# W5500.net
KiCad netlist of a schematic drawn in Altium Designer
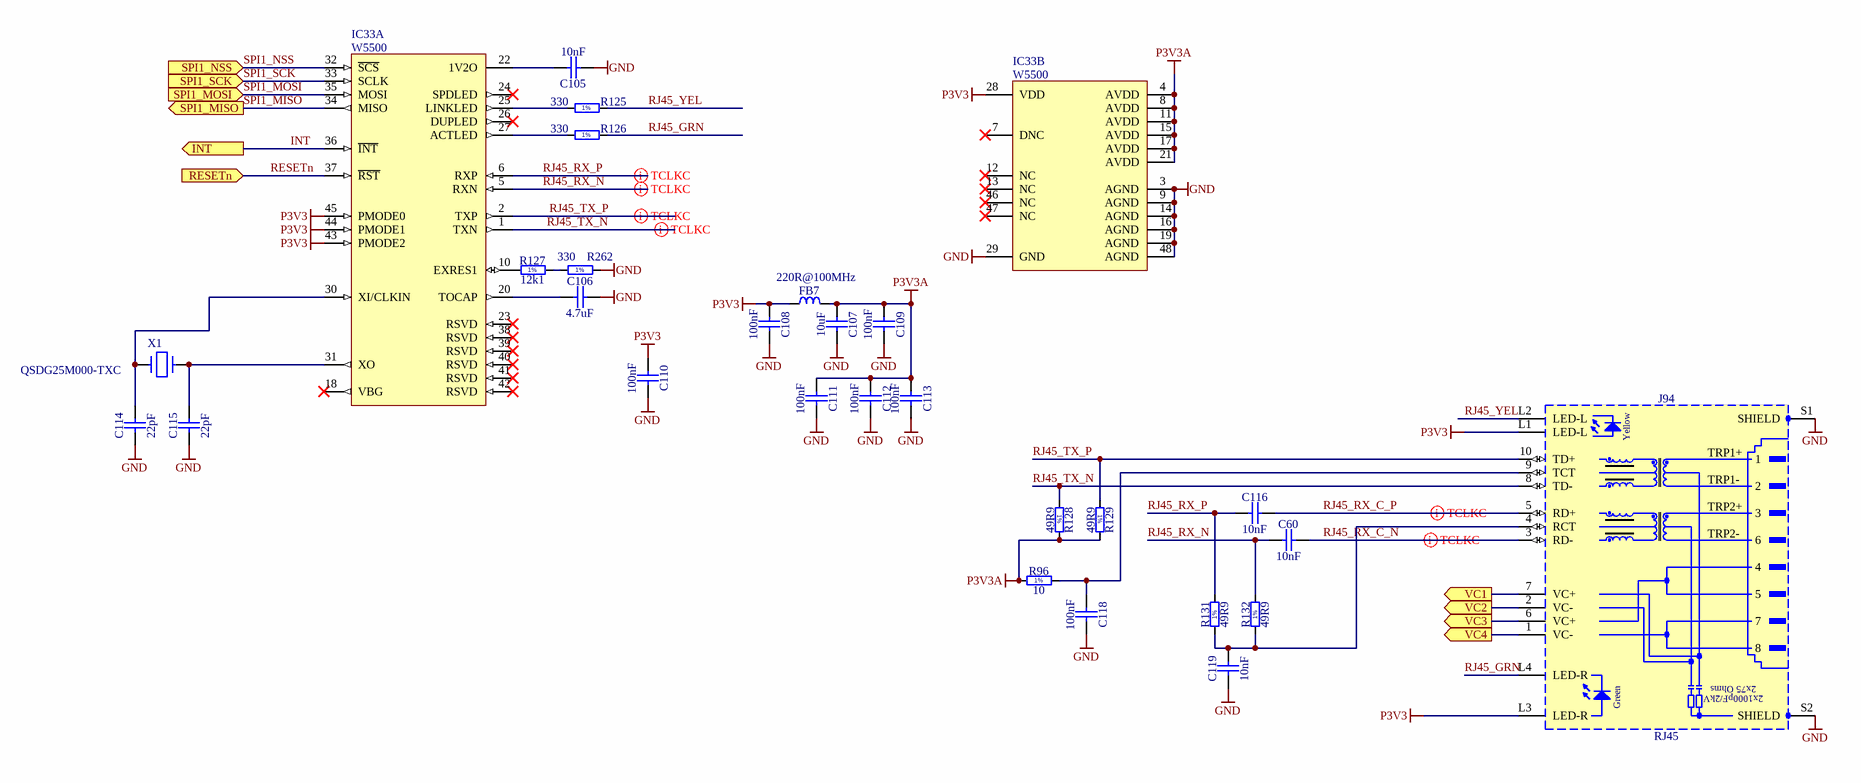
[diagram p0: W5500.SchDoc]

(export (version "E")
  (design (tool "Eeschema 10.0.6"))
  (components
    (comp (ref "C60")
      (value "10nF")
      (footprint "CAPC1608X87N")
      (description "Non-polarised capacitor")
      (fields
        (field (name "PART NUMBER") "CC0603_10NF_50V_5%_C0G")
        (field (name "VOLTAGE") "50V")
        (field (name "AUTHOR") "CERN DEM JLC")
      )
      (libsource (lib "Capacitors") (part "Capacitor - non polarized"))
    )
    (comp (ref "C105")
      (value "10nF")
      (footprint "CAPC1608X87N")
      (description "Non-polarised capacitor")
      (fields
        (field (name "PART NUMBER") "CC0603_10NF_50V_5%_C0G")
        (field (name "VOLTAGE") "50V")
        (field (name "AUTHOR") "CERN DEM JLC")
      )
      (libsource (lib "Capacitors") (part "Capacitor - non polarized"))
    )
    (comp (ref "C106")
      (value "4.7uF")
      (footprint "CAPC1608X90N")
      (description "Non-polarised capacitor")
      (fields
        (field (name "PART NUMBER") "CC0603_4.7UF_25V_10%_X5R")
        (field (name "VOLTAGE") "25V")
        (field (name "AUTHOR") "CERN DEM JLC")
      )
      (libsource (lib "Capacitors") (part "Capacitor - non polarized"))
    )
    (comp (ref "C107")
      (value "10uF")
      (footprint "CAPC2012X135N")
      (description "Non-polarised capacitor")
      (fields
        (field (name "PART NUMBER") "CC0805_10UF_16V_10%_X5R")
        (field (name "VOLTAGE") "16V")
        (field (name "AUTHOR") "CERN DEM JLC")
      )
      (libsource (lib "Capacitors") (part "Capacitor - non polarized"))
    )
    (comp (ref "C108")
      (value "100nF")
      (footprint "CAPC1005X55N")
      (description "Non-polarised capacitor")
      (fields
        (field (name "PART NUMBER") "CC0402_100NF_16V_10%_X7R")
        (field (name "VOLTAGE") "16V")
        (field (name "AUTHOR") "CERN DEM JLC")
      )
      (libsource (lib "Capacitors") (part "Capacitor - non polarized"))
    )
    (comp (ref "C109")
      (value "100nF")
      (footprint "CAPC1005X55N")
      (description "Non-polarised capacitor")
      (fields
        (field (name "PART NUMBER") "CC0402_100NF_16V_10%_X7R")
        (field (name "VOLTAGE") "16V")
        (field (name "AUTHOR") "CERN DEM JLC")
      )
      (libsource (lib "Capacitors") (part "Capacitor - non polarized"))
    )
    (comp (ref "C110")
      (value "100nF")
      (footprint "CAPC1005X55N")
      (description "Non-polarised capacitor")
      (fields
        (field (name "PART NUMBER") "CC0402_100NF_16V_10%_X7R")
        (field (name "VOLTAGE") "16V")
        (field (name "AUTHOR") "CERN DEM JLC")
      )
      (libsource (lib "Capacitors") (part "Capacitor - non polarized"))
    )
    (comp (ref "C111")
      (value "100nF")
      (footprint "CAPC1005X55N")
      (description "Non-polarised capacitor")
      (fields
        (field (name "PART NUMBER") "CC0402_100NF_16V_10%_X7R")
        (field (name "VOLTAGE") "16V")
        (field (name "AUTHOR") "CERN DEM JLC")
      )
      (libsource (lib "Capacitors") (part "Capacitor - non polarized"))
    )
    (comp (ref "C112")
      (value "100nF")
      (footprint "CAPC1005X55N")
      (description "Non-polarised capacitor")
      (fields
        (field (name "PART NUMBER") "CC0402_100NF_16V_10%_X7R")
        (field (name "VOLTAGE") "16V")
        (field (name "AUTHOR") "CERN DEM JLC")
      )
      (libsource (lib "Capacitors") (part "Capacitor - non polarized"))
    )
    (comp (ref "C113")
      (value "100nF")
      (footprint "CAPC1005X55N")
      (description "Non-polarised capacitor")
      (fields
        (field (name "PART NUMBER") "CC0402_100NF_16V_10%_X7R")
        (field (name "VOLTAGE") "16V")
        (field (name "AUTHOR") "CERN DEM JLC")
      )
      (libsource (lib "Capacitors") (part "Capacitor - non polarized"))
    )
    (comp (ref "C114")
      (value "22pF")
      (footprint "CAPC1005X55N")
      (description "Non-polarised capacitor")
      (fields
        (field (name "PART NUMBER") "CC0402_22PF_50V_5%_NP0")
        (field (name "VOLTAGE") "50V")
        (field (name "AUTHOR") "CERN DEM JLC")
      )
      (libsource (lib "Capacitors") (part "Capacitor - non polarized"))
    )
    (comp (ref "C115")
      (value "22pF")
      (footprint "CAPC1005X55N")
      (description "Non-polarised capacitor")
      (fields
        (field (name "PART NUMBER") "CC0402_22PF_50V_5%_NP0")
        (field (name "VOLTAGE") "50V")
        (field (name "AUTHOR") "CERN DEM JLC")
      )
      (libsource (lib "Capacitors") (part "Capacitor - non polarized"))
    )
    (comp (ref "C116")
      (value "10nF")
      (footprint "CAPC1608X87N")
      (description "Non-polarised capacitor")
      (fields
        (field (name "PART NUMBER") "CC0603_10NF_50V_5%_C0G")
        (field (name "VOLTAGE") "50V")
        (field (name "AUTHOR") "CERN DEM JLC")
      )
      (libsource (lib "Capacitors") (part "Capacitor - non polarized"))
    )
    (comp (ref "C118")
      (value "100nF")
      (footprint "CAPC1005X55N")
      (description "Non-polarised capacitor")
      (fields
        (field (name "PART NUMBER") "CC0402_100NF_16V_10%_X7R")
        (field (name "VOLTAGE") "16V")
        (field (name "AUTHOR") "CERN DEM JLC")
      )
      (libsource (lib "Capacitors") (part "Capacitor - non polarized"))
    )
    (comp (ref "C119")
      (value "10nF")
      (footprint "CAPC1608X87N")
      (description "Non-polarised capacitor")
      (fields
        (field (name "PART NUMBER") "CC0603_10NF_50V_5%_C0G")
        (field (name "VOLTAGE") "50V")
        (field (name "AUTHOR") "CERN DEM JLC")
      )
      (libsource (lib "Capacitors") (part "Capacitor - non polarized"))
    )
    (comp (ref "FB7")
      (value "220R@100MHz")
      (footprint "INDC2012X105N")
      (description "Inductor")
      (fields
        (field (name "PART NUMBER") "IND0805_MURATA_BLM21PG221SN1D")
        (field (name "POWER") "2A")
        (field (name "AUTHOR") "CERN DEM JLC")
      )
      (libsource (lib "Inductors & Transformers") (part "Inductor"))
    )
    (comp (ref "IC33")
      (value "W5500")
      (footprint "QFP50P900X900X160-48N")
      (description "iEthernet W5500 TCP/IP Performance and High Speed SPI Ethernet Controller")
      (fields (field (name "MANUFACTURER") "WIZNET") (field (name "AUTHOR") "CERN DEM MR"))
      (libsource (lib "ICs And Semiconductors") (part "W5500"))
    )
    (comp (ref "J94")
      (value "RJ45")
      (footprint "ABRACON_ARJM11C7-114-BA-EW2")
      (description "MagJack 10/100BaseT, PoE+, 1X1, OG/Y, -40 to 85*C, Tab Up, RoHS")
      (fields
        (field (name "PART NUMBER") "ARJM11C7-114-BA-EW2")
        (field (name "MANUFACTURER") "Abracon")
        (field (name "AUTHOR") "GK")
      )
      (libsource (lib "LIBRARY_SCH") (part "CON_ETH_POE_ARJM11C7"))
    )
    (comp (ref "R96")
      (value "10")
      (footprint "RESC1005X40N")
      (description "Resistor - 1%")
      (fields
        (field (name "PART NUMBER") "R0402_10R_1%_0.0625W_200PPM")
        (field (name "POWER") "0.0625W")
        (field (name "AUTHOR") "CERN DEM JLC")
      )
      (libsource (lib "Resistors") (part "Resistor - 1%"))
    )
    (comp (ref "R125")
      (value "330")
      (footprint "RESC1005X40N")
      (description "Resistor - 1%")
      (fields
        (field (name "PART NUMBER") "R0402_330R_1%_0.0625W_100PPM")
        (field (name "POWER") "0.0625W")
        (field (name "AUTHOR") "CERN DEM JLC")
      )
      (libsource (lib "Resistors") (part "Resistor - 1%"))
    )
    (comp (ref "R126")
      (value "330")
      (footprint "RESC1005X40N")
      (description "Resistor - 1%")
      (fields
        (field (name "PART NUMBER") "R0402_330R_1%_0.0625W_100PPM")
        (field (name "POWER") "0.0625W")
        (field (name "AUTHOR") "CERN DEM JLC")
      )
      (libsource (lib "Resistors") (part "Resistor - 1%"))
    )
    (comp (ref "R127")
      (value "12k1")
      (footprint "RESC1005X40N")
      (description "Resistor - 1%")
      (fields
        (field (name "PART NUMBER") "R0402_12K1_1%_0.0625W_100PPM")
        (field (name "POWER") "0.0625W")
        (field (name "AUTHOR") "CERN DEM JLC")
      )
      (libsource (lib "Resistors") (part "Resistor - 1%"))
    )
    (comp (ref "R128")
      (value "49R9")
      (footprint "RESC1005X40N")
      (description "Resistor - 1%")
      (fields
        (field (name "PART NUMBER") "R0402_49R9_1%_0.0625W_100PPM")
        (field (name "POWER") "0.0625W")
        (field (name "AUTHOR") "CERN DEM JLC")
      )
      (libsource (lib "Resistors") (part "Resistor - 1%"))
    )
    (comp (ref "R129")
      (value "49R9")
      (footprint "RESC1005X40N")
      (description "Resistor - 1%")
      (fields
        (field (name "PART NUMBER") "R0402_49R9_1%_0.0625W_100PPM")
        (field (name "POWER") "0.0625W")
        (field (name "AUTHOR") "CERN DEM JLC")
      )
      (libsource (lib "Resistors") (part "Resistor - 1%"))
    )
    (comp (ref "R131")
      (value "49R9")
      (footprint "RESC1005X40N")
      (description "Resistor - 1%")
      (fields
        (field (name "PART NUMBER") "R0402_49R9_1%_0.0625W_100PPM")
        (field (name "POWER") "0.0625W")
        (field (name "AUTHOR") "CERN DEM JLC")
      )
      (libsource (lib "Resistors") (part "Resistor - 1%"))
    )
    (comp (ref "R132")
      (value "49R9")
      (footprint "RESC1005X40N")
      (description "Resistor - 1%")
      (fields
        (field (name "PART NUMBER") "R0402_49R9_1%_0.0625W_100PPM")
        (field (name "POWER") "0.0625W")
        (field (name "AUTHOR") "CERN DEM JLC")
      )
      (libsource (lib "Resistors") (part "Resistor - 1%"))
    )
    (comp (ref "R262")
      (value "330")
      (footprint "RESC1005X40N")
      (description "Resistor - 1%")
      (fields
        (field (name "PART NUMBER") "R0402_330R_1%_0.0625W_100PPM")
        (field (name "POWER") "0.0625W")
        (field (name "AUTHOR") "CERN DEM JLC")
      )
      (libsource (lib "Resistors") (part "Resistor - 1%"))
    )
    (comp (ref "X1")
      (value "QSDG25M000-TXC")
      (footprint "XTAL_5.0*3.2")
      (description "miniature crystal oscillator (Maritex)")
      (libsource (lib "LIBRARY_SCH") (part "X_CRYSTAL_SMD_5.0*3.2"))
    )
  )
  (nets
    (net (code "1") (name "/INT") (class "Default")
      (node (ref "IC33") (pin "36") (pinfunction "~{INT}_36") (pintype "input"))
    )
    (net (code "2") (name "/RESETn") (class "Default")
      (node (ref "IC33") (pin "37") (pinfunction "~{RST}_37") (pintype "input"))
    )
    (net (code "3") (name "/RJ45_GRN") (class "Default")
      (node (ref "J94") (pin "L4") (pinfunction "LED-R_L4") (pintype "passive"))
      (node (ref "R126") (pin "2") (pinfunction "2_2") (pintype "passive"))
    )
    (net (code "4") (name "/RJ45_RX_C_N") (class "Default")
      (node (ref "C60") (pin "2") (pinfunction "2_2") (pintype "passive"))
      (node (ref "J94") (pin "3") (pinfunction "RD-_3") (pintype "bidirectional"))
    )
    (net (code "5") (name "/RJ45_RX_C_P") (class "Default")
      (node (ref "C116") (pin "2") (pinfunction "2_2") (pintype "passive"))
      (node (ref "J94") (pin "5") (pinfunction "RD+_5") (pintype "bidirectional"))
    )
    (net (code "6") (name "/RJ45_RX_N") (class "Default")
      (node (ref "C60") (pin "1") (pinfunction "1_1") (pintype "passive"))
      (node (ref "IC33") (pin "5") (pinfunction "RXN_5") (pintype "input"))
      (node (ref "R132") (pin "2") (pinfunction "2_2") (pintype "passive"))
    )
    (net (code "7") (name "/RJ45_RX_P") (class "Default")
      (node (ref "C116") (pin "1") (pinfunction "1_1") (pintype "passive"))
      (node (ref "IC33") (pin "6") (pinfunction "RXP_6") (pintype "input"))
      (node (ref "R131") (pin "2") (pinfunction "2_2") (pintype "passive"))
    )
    (net (code "8") (name "/RJ45_TX_N") (class "Default")
      (node (ref "IC33") (pin "1") (pinfunction "TXN_1") (pintype "output"))
      (node (ref "J94") (pin "8") (pinfunction "TD-_8") (pintype "bidirectional"))
      (node (ref "R128") (pin "1") (pinfunction "1_1") (pintype "passive"))
    )
    (net (code "9") (name "/RJ45_TX_P") (class "Default")
      (node (ref "IC33") (pin "2") (pinfunction "TXP_2") (pintype "output"))
      (node (ref "J94") (pin "10") (pinfunction "TD+_10") (pintype "bidirectional"))
      (node (ref "R129") (pin "1") (pinfunction "1_1") (pintype "passive"))
    )
    (net (code "10") (name "/RJ45_YEL") (class "Default")
      (node (ref "J94") (pin "L2") (pinfunction "LED-L_L2") (pintype "passive"))
      (node (ref "R125") (pin "2") (pinfunction "2_2") (pintype "passive"))
    )
    (net (code "11") (name "/SPI1_MISO") (class "Default")
      (node (ref "IC33") (pin "34") (pinfunction "MISO_34") (pintype "output"))
    )
    (net (code "12") (name "/SPI1_MOSI") (class "Default")
      (node (ref "IC33") (pin "35") (pinfunction "MOSI_35") (pintype "input"))
    )
    (net (code "13") (name "/SPI1_NSS") (class "Default")
      (node (ref "IC33") (pin "32") (pinfunction "~{SCS}_32") (pintype "input"))
    )
    (net (code "14") (name "/SPI1_SCK") (class "Default")
      (node (ref "IC33") (pin "33") (pinfunction "SCLK_33") (pintype "input"))
    )
    (net (code "15") (name "/VC1") (class "Default")
      (node (ref "J94") (pin "7") (pinfunction "VC+_7") (pintype "passive"))
    )
    (net (code "16") (name "/VC2") (class "Default")
      (node (ref "J94") (pin "2") (pinfunction "VC-_2") (pintype "passive"))
    )
    (net (code "17") (name "/VC3") (class "Default")
      (node (ref "J94") (pin "6") (pinfunction "VC+_6") (pintype "passive"))
    )
    (net (code "18") (name "/VC4") (class "Default")
      (node (ref "J94") (pin "1") (pinfunction "VC-_1") (pintype "passive"))
    )
    (net (code "19") (name "GND") (class "Default")
      (node (ref "C105") (pin "1") (pinfunction "1_1") (pintype "passive"))
      (node (ref "C106") (pin "2") (pinfunction "2_2") (pintype "passive"))
      (node (ref "C107") (pin "2") (pinfunction "2_2") (pintype "passive"))
      (node (ref "C108") (pin "2") (pinfunction "2_2") (pintype "passive"))
      (node (ref "C109") (pin "2") (pinfunction "2_2") (pintype "passive"))
      (node (ref "C110") (pin "2") (pinfunction "2_2") (pintype "passive"))
      (node (ref "C111") (pin "2") (pinfunction "2_2") (pintype "passive"))
      (node (ref "C112") (pin "2") (pinfunction "2_2") (pintype "passive"))
      (node (ref "C113") (pin "2") (pinfunction "2_2") (pintype "passive"))
      (node (ref "C114") (pin "1") (pinfunction "1_1") (pintype "passive"))
      (node (ref "C115") (pin "1") (pinfunction "1_1") (pintype "passive"))
      (node (ref "C118") (pin "2") (pinfunction "2_2") (pintype "passive"))
      (node (ref "C119") (pin "1") (pinfunction "1_1") (pintype "passive"))
      (node (ref "IC33") (pin "14") (pinfunction "AGND_14") (pintype "power_in"))
      (node (ref "IC33") (pin "16") (pinfunction "AGND_16") (pintype "power_in"))
      (node (ref "IC33") (pin "19") (pinfunction "AGND_19") (pintype "power_in"))
      (node (ref "IC33") (pin "29") (pinfunction "GND_29") (pintype "power_in"))
      (node (ref "IC33") (pin "3") (pinfunction "AGND_3") (pintype "power_in"))
      (node (ref "IC33") (pin "48") (pinfunction "AGND_48") (pintype "power_in"))
      (node (ref "IC33") (pin "9") (pinfunction "AGND_9") (pintype "power_in"))
      (node (ref "J94") (pin "S1") (pinfunction "SHIELD_S1") (pintype "power_in"))
      (node (ref "J94") (pin "S2") (pinfunction "SHIELD_S2") (pintype "power_in"))
      (node (ref "R262") (pin "2") (pinfunction "2_2") (pintype "passive"))
    )
    (net (code "20") (name "Net-(IC33A-1V2O)") (class "Default")
      (node (ref "C105") (pin "2") (pinfunction "2_2") (pintype "passive"))
      (node (ref "IC33") (pin "22") (pinfunction "1V2O_22") (pintype "power_in"))
    )
    (net (code "21") (name "Net-(IC33A-ACTLED)") (class "Default")
      (node (ref "IC33") (pin "27") (pinfunction "ACTLED_27") (pintype "output"))
      (node (ref "R126") (pin "1") (pinfunction "1_1") (pintype "passive"))
    )
    (net (code "22") (name "Net-(IC33A-EXRES1)") (class "Default")
      (node (ref "IC33") (pin "10") (pinfunction "EXRES1_10") (pintype "bidirectional"))
      (node (ref "R127") (pin "1") (pinfunction "1_1") (pintype "passive"))
    )
    (net (code "23") (name "Net-(IC33A-LINKLED)") (class "Default")
      (node (ref "IC33") (pin "25") (pinfunction "LINKLED_25") (pintype "output"))
      (node (ref "R125") (pin "1") (pinfunction "1_1") (pintype "passive"))
    )
    (net (code "24") (name "Net-(IC33A-TOCAP)") (class "Default")
      (node (ref "C106") (pin "1") (pinfunction "1_1") (pintype "passive"))
      (node (ref "IC33") (pin "20") (pinfunction "TOCAP_20") (pintype "output"))
    )
    (net (code "25") (name "Net-(IC33A-XI{slash}CLKIN)") (class "Default")
      (node (ref "C114") (pin "2") (pinfunction "2_2") (pintype "passive"))
      (node (ref "IC33") (pin "30") (pinfunction "XI/CLKIN_30") (pintype "input"))
      (node (ref "X1") (pin "1") (pinfunction "1_1") (pintype "passive"))
    )
    (net (code "26") (name "Net-(IC33A-XO)") (class "Default")
      (node (ref "C115") (pin "2") (pinfunction "2_2") (pintype "passive"))
      (node (ref "IC33") (pin "31") (pinfunction "XO_31") (pintype "output"))
      (node (ref "X1") (pin "2") (pinfunction "2_2") (pintype "passive"))
    )
    (net (code "27") (name "Net-(J94-RCT)") (class "Default")
      (node (ref "C119") (pin "2") (pinfunction "2_2") (pintype "passive"))
      (node (ref "J94") (pin "4") (pinfunction "RCT_4") (pintype "bidirectional"))
      (node (ref "R131") (pin "1") (pinfunction "1_1") (pintype "passive"))
      (node (ref "R132") (pin "1") (pinfunction "1_1") (pintype "passive"))
    )
    (net (code "28") (name "Net-(J94-TCT)") (class "Default")
      (node (ref "C118") (pin "1") (pinfunction "1_1") (pintype "passive"))
      (node (ref "J94") (pin "9") (pinfunction "TCT_9") (pintype "bidirectional"))
      (node (ref "R96") (pin "2") (pinfunction "2_2") (pintype "passive"))
    )
    (net (code "29") (name "Net-(R127-Pad2)") (class "Default")
      (node (ref "R127") (pin "2") (pinfunction "2_2") (pintype "passive"))
      (node (ref "R262") (pin "1") (pinfunction "1_1") (pintype "passive"))
    )
    (net (code "30") (name "P3V3") (class "Default")
      (node (ref "C108") (pin "1") (pinfunction "1_1") (pintype "passive"))
      (node (ref "C110") (pin "1") (pinfunction "1_1") (pintype "passive"))
      (node (ref "FB7") (pin "1") (pinfunction "1_1") (pintype "passive"))
      (node (ref "IC33") (pin "28") (pinfunction "VDD_28") (pintype "power_in"))
      (node (ref "IC33") (pin "43") (pinfunction "PMODE2_43") (pintype "input"))
      (node (ref "IC33") (pin "44") (pinfunction "PMODE1_44") (pintype "input"))
      (node (ref "IC33") (pin "45") (pinfunction "PMODE0_45") (pintype "input"))
      (node (ref "J94") (pin "L1") (pinfunction "LED-L_L1") (pintype "passive"))
      (node (ref "J94") (pin "L3") (pinfunction "LED-R_L3") (pintype "passive"))
    )
    (net (code "31") (name "P3V3A") (class "Default")
      (node (ref "C107") (pin "1") (pinfunction "1_1") (pintype "passive"))
      (node (ref "C109") (pin "1") (pinfunction "1_1") (pintype "passive"))
      (node (ref "C111") (pin "1") (pinfunction "1_1") (pintype "passive"))
      (node (ref "C112") (pin "1") (pinfunction "1_1") (pintype "passive"))
      (node (ref "C113") (pin "1") (pinfunction "1_1") (pintype "passive"))
      (node (ref "FB7") (pin "2") (pinfunction "2_2") (pintype "passive"))
      (node (ref "IC33") (pin "11") (pinfunction "AVDD_11") (pintype "power_in"))
      (node (ref "IC33") (pin "15") (pinfunction "AVDD_15") (pintype "power_in"))
      (node (ref "IC33") (pin "17") (pinfunction "AVDD_17") (pintype "power_in"))
      (node (ref "IC33") (pin "21") (pinfunction "AVDD_21") (pintype "power_in"))
      (node (ref "IC33") (pin "4") (pinfunction "AVDD_4") (pintype "power_in"))
      (node (ref "IC33") (pin "8") (pinfunction "AVDD_8") (pintype "power_in"))
      (node (ref "R128") (pin "2") (pinfunction "2_2") (pintype "passive"))
      (node (ref "R129") (pin "2") (pinfunction "2_2") (pintype "passive"))
      (node (ref "R96") (pin "1") (pinfunction "1_1") (pintype "passive"))
    )
    (net (code "32") (name "unconnected-(IC33A-DUPLED-Pad26)") (class "Default")
      (node (ref "IC33") (pin "26") (pinfunction "DUPLED_26") (pintype "output+no_connect"))
    )
    (net (code "33") (name "unconnected-(IC33A-RSVD-Pad23)") (class "Default")
      (node (ref "IC33") (pin "23") (pinfunction "RSVD_23") (pintype "input+no_connect"))
    )
    (net (code "34") (name "unconnected-(IC33A-RSVD-Pad38)") (class "Default")
      (node (ref "IC33") (pin "38") (pinfunction "RSVD_38") (pintype "input+no_connect"))
    )
    (net (code "35") (name "unconnected-(IC33A-RSVD-Pad39)") (class "Default")
      (node (ref "IC33") (pin "39") (pinfunction "RSVD_39") (pintype "input+no_connect"))
    )
    (net (code "36") (name "unconnected-(IC33A-RSVD-Pad40)") (class "Default")
      (node (ref "IC33") (pin "40") (pinfunction "RSVD_40") (pintype "input+no_connect"))
    )
    (net (code "37") (name "unconnected-(IC33A-RSVD-Pad41)") (class "Default")
      (node (ref "IC33") (pin "41") (pinfunction "RSVD_41") (pintype "input+no_connect"))
    )
    (net (code "38") (name "unconnected-(IC33A-RSVD-Pad42)") (class "Default")
      (node (ref "IC33") (pin "42") (pinfunction "RSVD_42") (pintype "input+no_connect"))
    )
    (net (code "39") (name "unconnected-(IC33A-SPDLED-Pad24)") (class "Default")
      (node (ref "IC33") (pin "24") (pinfunction "SPDLED_24") (pintype "output+no_connect"))
    )
    (net (code "40") (name "unconnected-(IC33A-VBG-Pad18)") (class "Default")
      (node (ref "IC33") (pin "18") (pinfunction "VBG_18") (pintype "output+no_connect"))
    )
    (net (code "41") (name "unconnected-(IC33B-DNC-Pad7)") (class "Default")
      (node (ref "IC33") (pin "7") (pinfunction "DNC_7") (pintype "passive+no_connect"))
    )
    (net (code "42") (name "unconnected-(IC33B-NC-Pad12)") (class "Default")
      (node (ref "IC33") (pin "12") (pinfunction "NC_12") (pintype "passive+no_connect"))
    )
    (net (code "43") (name "unconnected-(IC33B-NC-Pad13)") (class "Default")
      (node (ref "IC33") (pin "13") (pinfunction "NC_13") (pintype "passive+no_connect"))
    )
    (net (code "44") (name "unconnected-(IC33B-NC-Pad46)") (class "Default")
      (node (ref "IC33") (pin "46") (pinfunction "NC_46") (pintype "passive+no_connect"))
    )
    (net (code "45") (name "unconnected-(IC33B-NC-Pad47)") (class "Default")
      (node (ref "IC33") (pin "47") (pinfunction "NC_47") (pintype "passive+no_connect"))
    )
  )
)
